# Addon-mapleCUx_HM-RFM69-RFM95-V11-019.net
KiCad netlist of a schematic drawn in EAGLE
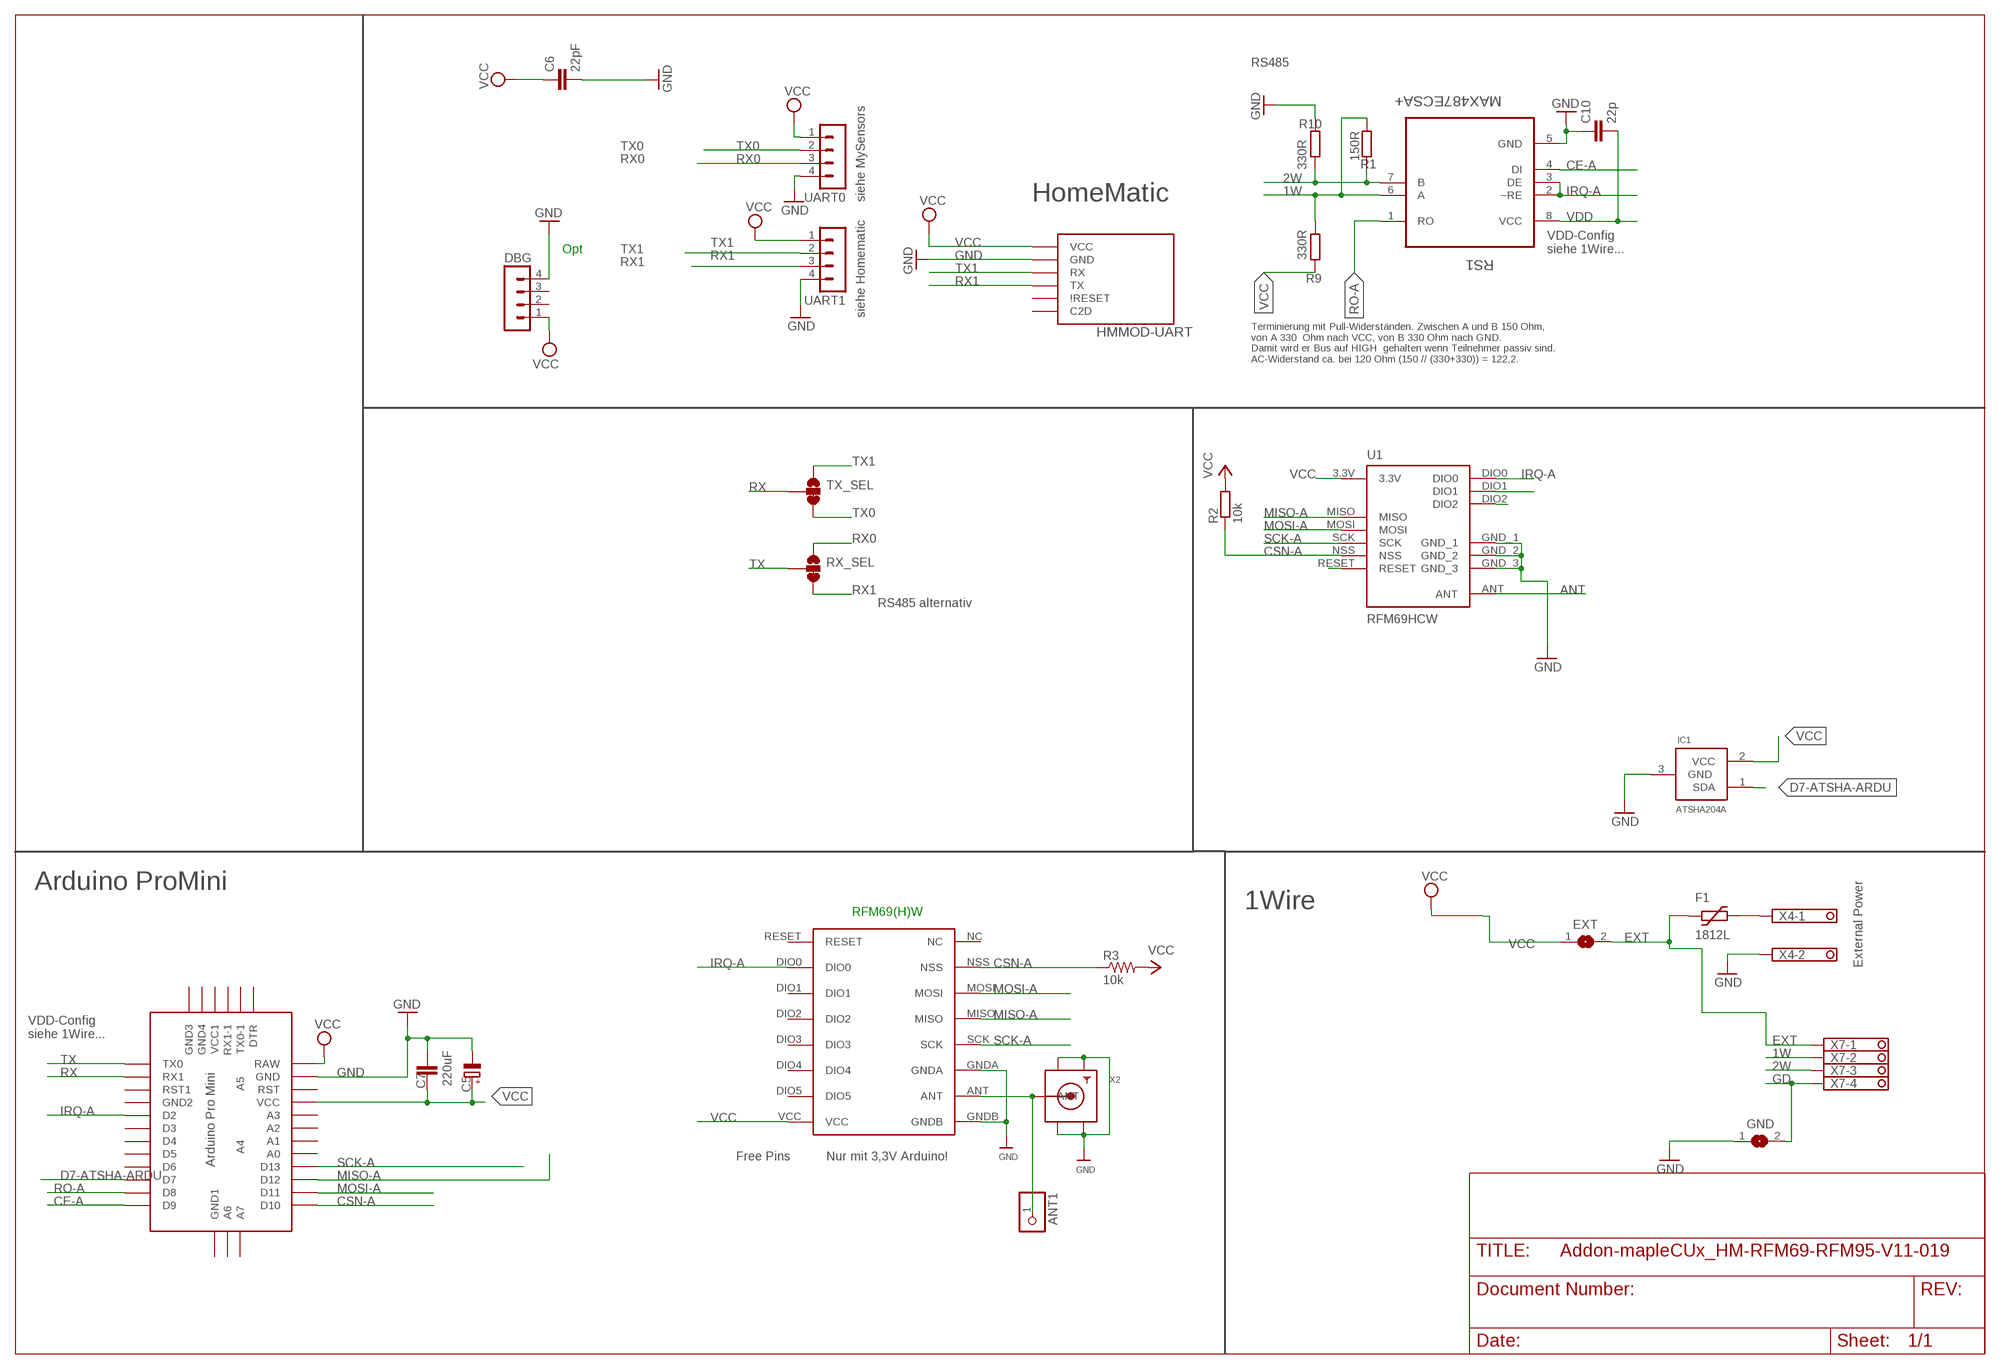
[diagram p0: schematic, sheet 1]

(export (version "E")
  (design (tool "Eeschema 10.0.6"))
  (components
    (comp (ref "ANT1")
      (value "PINHD-1X1")
      (footprint "eagle-import:1X01")
      (libsource (lib "eagle-import") (part "PINHD-1X1"))
    )
    (comp (ref "C5")
      (value "220uF")
      (footprint "eagle-import:E5-8,5")
      (libsource (lib "eagle-import") (part "CPOL-EUE5-8.5"))
    )
    (comp (ref "C6")
      (value "22pF")
      (footprint "eagle-import:C0805")
      (libsource (lib "eagle-import") (part "C-EUC0805"))
    )
    (comp (ref "C7")
      (value "C-EUC1812")
      (footprint "eagle-import:C1812")
      (libsource (lib "eagle-import") (part "C-EUC1812"))
    )
    (comp (ref "C10")
      (value "22p")
      (footprint "eagle-import:C0805")
      (libsource (lib "eagle-import") (part "C-EUC0805"))
    )
    (comp (ref "DBG")
      (value "MA04-1")
      (footprint "eagle-import:MA04-1")
      (libsource (lib "eagle-import") (part "MA04-1"))
    )
    (comp (ref "EXT") (value "SJ") (footprint "eagle-import:SJ") (libsource (lib "eagle-import") (part "SJ")))
    (comp (ref "F1")
      (value "1812L")
      (footprint "eagle-import:1812L")
      (libsource (lib "eagle-import") (part "1812L"))
    )
    (comp (ref "GND") (value "SJ") (footprint "eagle-import:SJ") (libsource (lib "eagle-import") (part "SJ")))
    (comp (ref "HMMOD-UART")
      (value "HM-MOD-UARTDIL")
      (footprint "eagle-import:HM-MOD-UART-DIL")
      (libsource (lib "eagle-import") (part "HM-MOD-UARTDIL"))
    )
    (comp (ref "IC1")
      (value "ATSHA204A")
      (footprint "eagle-import:SOT23")
      (libsource (lib "eagle-import") (part "ATSHA204A"))
    )
    (comp (ref "R1")
      (value "150R")
      (footprint "eagle-import:R0805")
      (libsource (lib "eagle-import") (part "R-EU_R0805"))
    )
    (comp (ref "R2")
      (value "10k")
      (footprint "eagle-import:M0805")
      (libsource (lib "eagle-import") (part "R-EU_M0805"))
    )
    (comp (ref "R3")
      (value "10k")
      (footprint "eagle-import:0805")
      (libsource (lib "eagle-import") (part "RESISTOR0805-RES"))
    )
    (comp (ref "R9")
      (value "330R")
      (footprint "eagle-import:R0805")
      (libsource (lib "eagle-import") (part "R-EU_R0805"))
    )
    (comp (ref "R10")
      (value "330R")
      (footprint "eagle-import:R0805")
      (libsource (lib "eagle-import") (part "R-EU_R0805"))
    )
    (comp (ref "RFM69W")
      (value "RFM69HW")
      (footprint "eagle-import:RFM")
      (libsource (lib "eagle-import") (part "RFM69HW"))
    )
    (comp (ref "RS1")
      (value "MAX487ECSA+")
      (footprint "eagle-import:SOIC127P600X175-8N")
      (libsource (lib "eagle-import") (part "MAX487ECSA+"))
    )
    (comp (ref "RX_SEL")
      (value "JUMPER-SMT_3_1-NC_TRACE_SILK")
      (footprint "eagle-import:SMT-JUMPER_3_1-NC_TRACE_SILK")
      (libsource (lib "eagle-import") (part "JUMPER-SMT_3_1-NC_TRACE_SILK"))
    )
    (comp (ref "TX_SEL")
      (value "JUMPER-SMT_3_1-NC_TRACE_SILK")
      (footprint "eagle-import:SMT-JUMPER_3_1-NC_TRACE_SILK")
      (libsource (lib "eagle-import") (part "JUMPER-SMT_3_1-NC_TRACE_SILK"))
    )
    (comp (ref "U$2")
      (value "ABK-PRO-MINI")
      (footprint "eagle-import:ABK-PRO-MINI")
      (libsource (lib "eagle-import") (part "ABK-PRO-MINI"))
    )
    (comp (ref "U1")
      (value "RFM69HCW")
      (footprint "eagle-import:RFM69HCW-XXXS2")
      (libsource (lib "eagle-import") (part "RFM69HCW"))
    )
    (comp (ref "UART0")
      (value "MA04-1")
      (footprint "eagle-import:MA04-1")
      (libsource (lib "eagle-import") (part "MA04-1"))
    )
    (comp (ref "UART1")
      (value "MA04-1")
      (footprint "eagle-import:MA04-1")
      (libsource (lib "eagle-import") (part "MA04-1"))
    )
    (comp (ref "X2")
      (value "SMACONNECTOR_EDGE")
      (footprint "eagle-import:SMA_EDGELAUNCH")
      (libsource (lib "eagle-import") (part "SMACONNECTOR_EDGE"))
    )
    (comp (ref "X4")
      (value "1751248")
      (footprint "eagle-import:1751248")
      (libsource (lib "eagle-import") (part "1751248"))
    )
    (comp (ref "X7")
      (value "1751264")
      (footprint "eagle-import:1751264")
      (libsource (lib "eagle-import") (part "1751264"))
    )
  )
  (nets
    (net (code "1") (name "/1W") (class "Default")
      (node (ref "R1") (pin "1") (pinfunction "1_1") (pintype "passive"))
      (node (ref "R9") (pin "2") (pinfunction "2_2") (pintype "passive"))
      (node (ref "RS1") (pin "6") (pinfunction "A_6") (pintype "bidirectional"))
      (node (ref "X7") (pin "2") (pinfunction "K_2") (pintype "passive"))
    )
    (net (code "2") (name "/2W") (class "Default")
      (node (ref "R1") (pin "2") (pinfunction "2_2") (pintype "passive"))
      (node (ref "R10") (pin "1") (pinfunction "1_1") (pintype "passive"))
      (node (ref "RS1") (pin "7") (pinfunction "B_7") (pintype "bidirectional"))
      (node (ref "X7") (pin "3") (pinfunction "K_3") (pintype "passive"))
    )
    (net (code "3") (name "/ANT") (class "Default")
      (node (ref "ANT1") (pin "1") (pinfunction "1_1") (pintype "passive"))
      (node (ref "RFM69W") (pin "ANT") (pinfunction "ANT_ANT") (pintype "bidirectional"))
      (node (ref "U1") (pin "ANT") (pinfunction "ANT_ANT") (pintype "passive"))
      (node (ref "X2") (pin "P") (pinfunction "ANT_P") (pintype "bidirectional"))
    )
    (net (code "4") (name "/CE-A") (class "Default")
      (node (ref "RS1") (pin "4") (pinfunction "DI_4") (pintype "input"))
      (node (ref "U$2") (pin "D9") (pinfunction "D9_D9") (pintype "bidirectional"))
    )
    (net (code "5") (name "/CSN-A") (class "Default")
      (node (ref "R2") (pin "1") (pinfunction "1_1") (pintype "passive"))
      (node (ref "R3") (pin "1") (pinfunction "1_1") (pintype "passive"))
      (node (ref "RFM69W") (pin "NSS") (pinfunction "NSS_NSS") (pintype "bidirectional"))
      (node (ref "U$2") (pin "D10") (pinfunction "D10_D10") (pintype "bidirectional"))
      (node (ref "U1") (pin "NSS") (pinfunction "NSS_NSS") (pintype "input"))
    )
    (net (code "6") (name "/EXT") (class "Default")
      (node (ref "EXT") (pin "2") (pinfunction "2_2") (pintype "passive"))
      (node (ref "F1") (pin "P$1") (pinfunction "1_P$1") (pintype "passive"))
      (node (ref "X7") (pin "1") (pinfunction "K_1") (pintype "passive"))
    )
    (net (code "7") (name "/GD") (class "Default")
      (node (ref "GND") (pin "2") (pinfunction "2_2") (pintype "passive"))
      (node (ref "X7") (pin "4") (pinfunction "K_4") (pintype "passive"))
    )
    (net (code "8") (name "/IRQ-A") (class "Default")
      (node (ref "RFM69W") (pin "DIO0") (pinfunction "DIO0_DIO0") (pintype "bidirectional"))
      (node (ref "RS1") (pin "2") (pinfunction "~{RE}_2") (pintype "input"))
      (node (ref "RS1") (pin "3") (pinfunction "DE_3") (pintype "input"))
      (node (ref "U$2") (pin "D2") (pinfunction "D2_D2") (pintype "bidirectional"))
      (node (ref "U1") (pin "DIO0") (pinfunction "DIO0_DIO0") (pintype "bidirectional"))
    )
    (net (code "9") (name "/MISO-A") (class "Default")
      (node (ref "RFM69W") (pin "MISO") (pinfunction "MISO_MISO") (pintype "bidirectional"))
      (node (ref "U$2") (pin "D12") (pinfunction "D12_D12") (pintype "bidirectional"))
      (node (ref "U1") (pin "MISO") (pinfunction "MISO_MISO") (pintype "bidirectional"))
    )
    (net (code "10") (name "/MOSI-A") (class "Default")
      (node (ref "RFM69W") (pin "MOSI") (pinfunction "MOSI_MOSI") (pintype "bidirectional"))
      (node (ref "U$2") (pin "D11") (pinfunction "D11_D11") (pintype "bidirectional"))
      (node (ref "U1") (pin "MOSI") (pinfunction "MOSI_MOSI") (pintype "input"))
    )
    (net (code "11") (name "/RX") (class "Default")
      (node (ref "TX_SEL") (pin "2") (pinfunction "2_2") (pintype "passive"))
      (node (ref "U$2") (pin "RX1") (pinfunction "RX1_RX1") (pintype "bidirectional"))
    )
    (net (code "12") (name "/RX0") (class "Default")
      (node (ref "RX_SEL") (pin "1") (pinfunction "1_1") (pintype "passive"))
      (node (ref "UART0") (pin "3") (pinfunction "3_3") (pintype "passive"))
    )
    (net (code "13") (name "/RX1") (class "Default")
      (node (ref "HMMOD-UART") (pin "5") (pinfunction "TX_5") (pintype "bidirectional"))
      (node (ref "RX_SEL") (pin "3") (pinfunction "3_3") (pintype "passive"))
      (node (ref "UART1") (pin "3") (pinfunction "3_3") (pintype "passive"))
    )
    (net (code "14") (name "/SCK-A") (class "Default")
      (node (ref "RFM69W") (pin "SCK") (pinfunction "SCK_SCK") (pintype "bidirectional"))
      (node (ref "U$2") (pin "D13") (pinfunction "D13_D13") (pintype "bidirectional"))
      (node (ref "U1") (pin "SCK") (pinfunction "SCK_SCK") (pintype "input"))
    )
    (net (code "15") (name "/TX") (class "Default")
      (node (ref "RX_SEL") (pin "2") (pinfunction "2_2") (pintype "passive"))
      (node (ref "U$2") (pin "TX0") (pinfunction "TX0_TX0") (pintype "bidirectional"))
    )
    (net (code "16") (name "/TX0") (class "Default")
      (node (ref "TX_SEL") (pin "3") (pinfunction "3_3") (pintype "passive"))
      (node (ref "UART0") (pin "2") (pinfunction "2_2") (pintype "passive"))
    )
    (net (code "17") (name "/TX1") (class "Default")
      (node (ref "HMMOD-UART") (pin "6") (pinfunction "RX_6") (pintype "bidirectional"))
      (node (ref "TX_SEL") (pin "1") (pinfunction "1_1") (pintype "passive"))
      (node (ref "UART1") (pin "2") (pinfunction "2_2") (pintype "passive"))
    )
    (net (code "18") (name "/VDD") (class "Default")
      (node (ref "C10") (pin "2") (pinfunction "2_2") (pintype "passive"))
      (node (ref "RS1") (pin "8") (pinfunction "VCC_8") (pintype "power_in"))
    )
    (net (code "19") (name "D7-ATSHA-ARDU") (class "Default")
      (node (ref "IC1") (pin "1") (pinfunction "SDA_1") (pintype "bidirectional"))
      (node (ref "U$2") (pin "D7") (pinfunction "D7_D7") (pintype "bidirectional"))
    )
    (net (code "20") (name "GND") (class "Default")
      (node (ref "C10") (pin "1") (pinfunction "1_1") (pintype "passive"))
      (node (ref "C5") (pin "-") (pinfunction "-_-") (pintype "passive"))
      (node (ref "C6") (pin "2") (pinfunction "2_2") (pintype "passive"))
      (node (ref "C7") (pin "1") (pinfunction "1_1") (pintype "passive"))
      (node (ref "DBG") (pin "4") (pinfunction "4_4") (pintype "passive"))
      (node (ref "GND") (pin "1") (pinfunction "1_1") (pintype "passive"))
      (node (ref "HMMOD-UART") (pin "2") (pinfunction "GND_2") (pintype "power_in"))
      (node (ref "IC1") (pin "3") (pinfunction "GND_3") (pintype "bidirectional"))
      (node (ref "R10") (pin "2") (pinfunction "2_2") (pintype "passive"))
      (node (ref "RFM69W") (pin "GNDA") (pinfunction "GNDA_GNDA") (pintype "bidirectional"))
      (node (ref "RFM69W") (pin "GNDB") (pinfunction "GNDB_GNDB") (pintype "bidirectional"))
      (node (ref "RS1") (pin "5") (pinfunction "GND_5") (pintype "passive"))
      (node (ref "U$2") (pin "GND") (pinfunction "GND_GND") (pintype "bidirectional"))
      (node (ref "U1") (pin "GND_1") (pinfunction "GND_1_GND_1") (pintype "power_in"))
      (node (ref "U1") (pin "GND_2") (pinfunction "GND_2_GND_2") (pintype "power_in"))
      (node (ref "U1") (pin "GND_3") (pinfunction "GND_3_GND_3") (pintype "power_in"))
      (node (ref "UART0") (pin "4") (pinfunction "4_4") (pintype "passive"))
      (node (ref "UART1") (pin "4") (pinfunction "4_4") (pintype "passive"))
      (node (ref "X2") (pin "GND@1") (pinfunction "GND4_GND@1") (pintype "power_in"))
      (node (ref "X2") (pin "GND@2") (pinfunction "GND3_GND@2") (pintype "power_in"))
      (node (ref "X2") (pin "GND@3") (pinfunction "GND2_GND@3") (pintype "power_in"))
      (node (ref "X2") (pin "GND@4") (pinfunction "GND1_GND@4") (pintype "power_in"))
      (node (ref "X4") (pin "2") (pinfunction "K_2") (pintype "passive"))
    )
    (net (code "21") (name "Net-(F1-2)") (class "Default")
      (node (ref "F1") (pin "P$2") (pinfunction "2_P$2") (pintype "passive"))
      (node (ref "X4") (pin "1") (pinfunction "K_1") (pintype "passive"))
    )
    (net (code "22") (name "RO-A") (class "Default")
      (node (ref "RS1") (pin "1") (pinfunction "RO_1") (pintype "output"))
      (node (ref "U$2") (pin "D8") (pinfunction "D8_D8") (pintype "bidirectional"))
    )
    (net (code "23") (name "VCC") (class "Default")
      (node (ref "C5") (pin "+") (pinfunction "+_+") (pintype "passive"))
      (node (ref "C6") (pin "1") (pinfunction "1_1") (pintype "passive"))
      (node (ref "C7") (pin "2") (pinfunction "2_2") (pintype "passive"))
      (node (ref "DBG") (pin "1") (pinfunction "1_1") (pintype "passive"))
      (node (ref "EXT") (pin "1") (pinfunction "1_1") (pintype "passive"))
      (node (ref "HMMOD-UART") (pin "1") (pinfunction "VCC_1") (pintype "power_in"))
      (node (ref "IC1") (pin "2") (pinfunction "VCC_2") (pintype "bidirectional"))
      (node (ref "R2") (pin "2") (pinfunction "2_2") (pintype "passive"))
      (node (ref "R3") (pin "2") (pinfunction "2_2") (pintype "passive"))
      (node (ref "R9") (pin "1") (pinfunction "1_1") (pintype "passive"))
      (node (ref "RFM69W") (pin "VCC") (pinfunction "VCC_VCC") (pintype "bidirectional"))
      (node (ref "U$2") (pin "RAW") (pinfunction "RAW_RAW") (pintype "bidirectional"))
      (node (ref "U$2") (pin "VCC") (pinfunction "VCC_VCC") (pintype "bidirectional"))
      (node (ref "U1") (pin "3.3V") (pinfunction "3.3V_3.3V") (pintype "power_in"))
      (node (ref "UART0") (pin "1") (pinfunction "1_1") (pintype "passive"))
      (node (ref "UART1") (pin "1") (pinfunction "1_1") (pintype "passive"))
    )
    (net (code "24") (name "unconnected-(DBG-Pad2)") (class "Default")
      (node (ref "DBG") (pin "2") (pinfunction "2_2") (pintype "passive"))
    )
    (net (code "25") (name "unconnected-(DBG-Pad3)") (class "Default")
      (node (ref "DBG") (pin "3") (pinfunction "3_3") (pintype "passive"))
    )
    (net (code "26") (name "unconnected-(HMMOD-UART-C2D-Pad3)") (class "Default")
      (node (ref "HMMOD-UART") (pin "3") (pinfunction "C2D_3") (pintype "bidirectional"))
    )
    (net (code "27") (name "unconnected-(HMMOD-UART-\\~{RESET}-Pad4)") (class "Default")
      (node (ref "HMMOD-UART") (pin "4") (pinfunction "\\~{RESET}_4") (pintype "bidirectional"))
    )
    (net (code "28") (name "unconnected-(RFM69W-PadDIO1)") (class "Default")
      (node (ref "RFM69W") (pin "DIO1") (pinfunction "DIO1_DIO1") (pintype "bidirectional"))
    )
    (net (code "29") (name "unconnected-(RFM69W-PadDIO2)") (class "Default")
      (node (ref "RFM69W") (pin "DIO2") (pinfunction "DIO2_DIO2") (pintype "bidirectional"))
    )
    (net (code "30") (name "unconnected-(RFM69W-PadDIO3)") (class "Default")
      (node (ref "RFM69W") (pin "DIO3") (pinfunction "DIO3_DIO3") (pintype "bidirectional"))
    )
    (net (code "31") (name "unconnected-(RFM69W-PadDIO4)") (class "Default")
      (node (ref "RFM69W") (pin "DIO4") (pinfunction "DIO4_DIO4") (pintype "bidirectional"))
    )
    (net (code "32") (name "unconnected-(RFM69W-PadDIO5)") (class "Default")
      (node (ref "RFM69W") (pin "DIO5") (pinfunction "DIO5_DIO5") (pintype "bidirectional"))
    )
    (net (code "33") (name "unconnected-(RFM69W-PadNC)") (class "Default")
      (node (ref "RFM69W") (pin "NC") (pinfunction "NC_NC") (pintype "bidirectional"))
    )
    (net (code "34") (name "unconnected-(RFM69W-PadRESET)") (class "Default")
      (node (ref "RFM69W") (pin "RESET") (pinfunction "RESET_RESET") (pintype "bidirectional"))
    )
    (net (code "35") (name "unconnected-(U$2-GND1-PadGND4)") (class "Default")
      (node (ref "U$2") (pin "GND4") (pinfunction "GND1_GND4") (pintype "bidirectional"))
    )
    (net (code "36") (name "unconnected-(U$2-GND2-PadGND1)") (class "Default")
      (node (ref "U$2") (pin "GND1") (pinfunction "GND2_GND1") (pintype "bidirectional"))
    )
    (net (code "37") (name "unconnected-(U$2-GND3-PadGND2)") (class "Default")
      (node (ref "U$2") (pin "GND2") (pinfunction "GND3_GND2") (pintype "bidirectional"))
    )
    (net (code "38") (name "unconnected-(U$2-GND4-PadGND3)") (class "Default")
      (node (ref "U$2") (pin "GND3") (pinfunction "GND4_GND3") (pintype "bidirectional"))
    )
    (net (code "39") (name "unconnected-(U$2-PadA0)") (class "Default")
      (node (ref "U$2") (pin "A0") (pinfunction "A0_A0") (pintype "bidirectional"))
    )
    (net (code "40") (name "unconnected-(U$2-PadA1)") (class "Default")
      (node (ref "U$2") (pin "A1") (pinfunction "A1_A1") (pintype "bidirectional"))
    )
    (net (code "41") (name "unconnected-(U$2-PadA2)") (class "Default")
      (node (ref "U$2") (pin "A2") (pinfunction "A2_A2") (pintype "bidirectional"))
    )
    (net (code "42") (name "unconnected-(U$2-PadA3)") (class "Default")
      (node (ref "U$2") (pin "A3") (pinfunction "A3_A3") (pintype "bidirectional"))
    )
    (net (code "43") (name "unconnected-(U$2-PadA4)") (class "Default")
      (node (ref "U$2") (pin "A4") (pinfunction "A4_A4") (pintype "bidirectional"))
    )
    (net (code "44") (name "unconnected-(U$2-PadA5)") (class "Default")
      (node (ref "U$2") (pin "A5") (pinfunction "A5_A5") (pintype "bidirectional"))
    )
    (net (code "45") (name "unconnected-(U$2-PadA6)") (class "Default")
      (node (ref "U$2") (pin "A6") (pinfunction "A6_A6") (pintype "bidirectional"))
    )
    (net (code "46") (name "unconnected-(U$2-PadA7)") (class "Default")
      (node (ref "U$2") (pin "A7") (pinfunction "A7_A7") (pintype "bidirectional"))
    )
    (net (code "47") (name "unconnected-(U$2-PadD3)") (class "Default")
      (node (ref "U$2") (pin "D3") (pinfunction "D3_D3") (pintype "bidirectional"))
    )
    (net (code "48") (name "unconnected-(U$2-PadD4)") (class "Default")
      (node (ref "U$2") (pin "D4") (pinfunction "D4_D4") (pintype "bidirectional"))
    )
    (net (code "49") (name "unconnected-(U$2-PadD5)") (class "Default")
      (node (ref "U$2") (pin "D5") (pinfunction "D5_D5") (pintype "bidirectional"))
    )
    (net (code "50") (name "unconnected-(U$2-PadD6)") (class "Default")
      (node (ref "U$2") (pin "D6") (pinfunction "D6_D6") (pintype "bidirectional"))
    )
    (net (code "51") (name "unconnected-(U$2-PadDTR)") (class "Default")
      (node (ref "U$2") (pin "DTR") (pinfunction "DTR_DTR") (pintype "bidirectional"))
    )
    (net (code "52") (name "unconnected-(U$2-PadRST)") (class "Default")
      (node (ref "U$2") (pin "RST") (pinfunction "RST_RST") (pintype "bidirectional"))
    )
    (net (code "53") (name "unconnected-(U$2-PadRST1)") (class "Default")
      (node (ref "U$2") (pin "RST1") (pinfunction "RST1_RST1") (pintype "bidirectional"))
    )
    (net (code "54") (name "unconnected-(U$2-PadRX1-1)") (class "Default")
      (node (ref "U$2") (pin "RX1-1") (pinfunction "RX1-1_RX1-1") (pintype "bidirectional"))
    )
    (net (code "55") (name "unconnected-(U$2-PadTX0-1)") (class "Default")
      (node (ref "U$2") (pin "TX0-1") (pinfunction "TX0-1_TX0-1") (pintype "bidirectional"))
    )
    (net (code "56") (name "unconnected-(U$2-PadVCC1)") (class "Default")
      (node (ref "U$2") (pin "VCC1") (pinfunction "VCC1_VCC1") (pintype "bidirectional"))
    )
    (net (code "57") (name "unconnected-(U1-PadDIO1)") (class "Default")
      (node (ref "U1") (pin "DIO1") (pinfunction "DIO1_DIO1") (pintype "bidirectional"))
    )
    (net (code "58") (name "unconnected-(U1-PadDIO2)") (class "Default")
      (node (ref "U1") (pin "DIO2") (pinfunction "DIO2_DIO2") (pintype "bidirectional"))
    )
    (net (code "59") (name "unconnected-(U1-PadRESET)") (class "Default")
      (node (ref "U1") (pin "RESET") (pinfunction "RESET_RESET") (pintype "input"))
    )
  )
)
